# v1.net
KiCad netlist of a schematic drawn in EAGLE
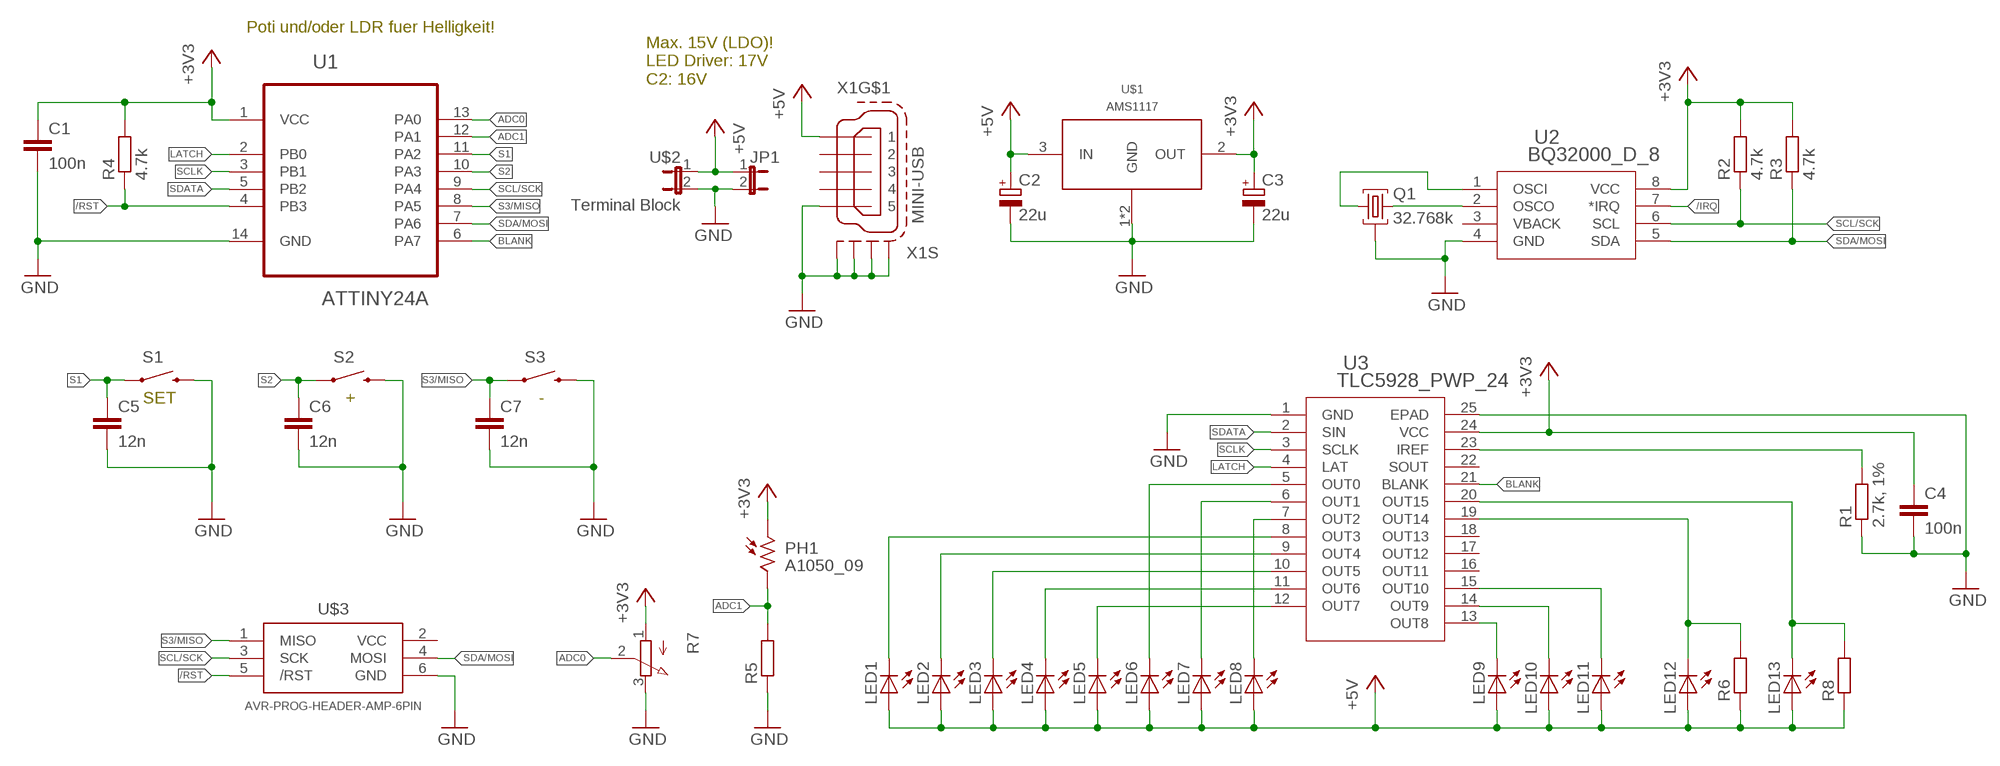
[diagram p0: schematic, sheet 1]
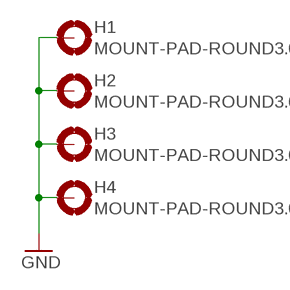
[diagram p1: schematic, sheet 2]

(export (version "E")
  (design (tool "Eeschema 10.0.6"))
  (components
    (comp (ref "C1")
      (value "100n")
      (footprint "eagle-import:C0603")
      (libsource (lib "eagle-import") (part "C-EUC0603"))
    )
    (comp (ref "C2")
      (value "22u")
      (footprint "eagle-import:153CLV-0505")
      (libsource (lib "eagle-import") (part "CPOL-EU153CLV-0505"))
    )
    (comp (ref "C3")
      (value "22u")
      (footprint "eagle-import:153CLV-0505")
      (libsource (lib "eagle-import") (part "CPOL-EU153CLV-0505"))
    )
    (comp (ref "C4")
      (value "100n")
      (footprint "eagle-import:C0603")
      (libsource (lib "eagle-import") (part "C-EUC0603"))
    )
    (comp (ref "C5")
      (value "12n")
      (footprint "eagle-import:C0603")
      (libsource (lib "eagle-import") (part "C-EUC0603"))
    )
    (comp (ref "C6")
      (value "12n")
      (footprint "eagle-import:C0603")
      (libsource (lib "eagle-import") (part "C-EUC0603"))
    )
    (comp (ref "C7")
      (value "12n")
      (footprint "eagle-import:C0603")
      (libsource (lib "eagle-import") (part "C-EUC0603"))
    )
    (comp (ref "JP1")
      (value "JP1E")
      (footprint "eagle-import:JP1")
      (libsource (lib "eagle-import") (part "JP1E"))
    )
    (comp (ref "LED1")
      (value "LEDCHIP-LED0603")
      (footprint "eagle-import:CHIP-LED0603")
      (libsource (lib "eagle-import") (part "LEDCHIP-LED0603"))
    )
    (comp (ref "LED2")
      (value "LEDCHIP-LED0603")
      (footprint "eagle-import:CHIP-LED0603")
      (libsource (lib "eagle-import") (part "LEDCHIP-LED0603"))
    )
    (comp (ref "LED3")
      (value "LEDCHIP-LED0603")
      (footprint "eagle-import:CHIP-LED0603")
      (libsource (lib "eagle-import") (part "LEDCHIP-LED0603"))
    )
    (comp (ref "LED4")
      (value "LEDCHIP-LED0603")
      (footprint "eagle-import:CHIP-LED0603")
      (libsource (lib "eagle-import") (part "LEDCHIP-LED0603"))
    )
    (comp (ref "LED5")
      (value "LEDCHIP-LED0603")
      (footprint "eagle-import:CHIP-LED0603")
      (libsource (lib "eagle-import") (part "LEDCHIP-LED0603"))
    )
    (comp (ref "LED6")
      (value "LEDCHIP-LED0603")
      (footprint "eagle-import:CHIP-LED0603")
      (libsource (lib "eagle-import") (part "LEDCHIP-LED0603"))
    )
    (comp (ref "LED7")
      (value "LEDCHIP-LED0603")
      (footprint "eagle-import:CHIP-LED0603")
      (libsource (lib "eagle-import") (part "LEDCHIP-LED0603"))
    )
    (comp (ref "LED8")
      (value "LEDCHIP-LED0603")
      (footprint "eagle-import:CHIP-LED0603")
      (libsource (lib "eagle-import") (part "LEDCHIP-LED0603"))
    )
    (comp (ref "LED9")
      (value "LEDCHIP-LED0603")
      (footprint "eagle-import:CHIP-LED0603")
      (libsource (lib "eagle-import") (part "LEDCHIP-LED0603"))
    )
    (comp (ref "LED10")
      (value "LEDCHIP-LED0603")
      (footprint "eagle-import:CHIP-LED0603")
      (libsource (lib "eagle-import") (part "LEDCHIP-LED0603"))
    )
    (comp (ref "LED11")
      (value "LEDCHIP-LED0603")
      (footprint "eagle-import:CHIP-LED0603")
      (libsource (lib "eagle-import") (part "LEDCHIP-LED0603"))
    )
    (comp (ref "LED12")
      (value "LEDCHIP-LED0603")
      (footprint "eagle-import:CHIP-LED0603")
      (libsource (lib "eagle-import") (part "LEDCHIP-LED0603"))
    )
    (comp (ref "LED13")
      (value "LEDCHIP-LED0603")
      (footprint "eagle-import:CHIP-LED0603")
      (libsource (lib "eagle-import") (part "LEDCHIP-LED0603"))
    )
    (comp (ref "PH1")
      (value "A1050_09")
      (footprint "eagle-import:T0-46-A10XX")
      (libsource (lib "eagle-import") (part "A1050_09"))
    )
    (comp (ref "Q1")
      (value "32.768k")
      (footprint "eagle-import:TC38")
      (libsource (lib "eagle-import") (part "CRYSTAL_TC38_SHIELD"))
    )
    (comp (ref "R1")
      (value "2.7k, 1%")
      (footprint "eagle-import:R1206")
      (libsource (lib "eagle-import") (part "R-EU_R1206"))
    )
    (comp (ref "R2")
      (value "4.7k")
      (footprint "eagle-import:R0603")
      (libsource (lib "eagle-import") (part "R-EU_R0603"))
    )
    (comp (ref "R3")
      (value "4.7k")
      (footprint "eagle-import:R0603")
      (libsource (lib "eagle-import") (part "R-EU_R0603"))
    )
    (comp (ref "R4")
      (value "4.7k")
      (footprint "eagle-import:R0603")
      (libsource (lib "eagle-import") (part "R-EU_R0603"))
    )
    (comp (ref "R5")
      (value "R-EU_R0603")
      (footprint "eagle-import:R0603")
      (libsource (lib "eagle-import") (part "R-EU_R0603"))
    )
    (comp (ref "R6")
      (value "R-EU_R0603")
      (footprint "eagle-import:R0603")
      (libsource (lib "eagle-import") (part "R-EU_R0603"))
    )
    (comp (ref "R7")
      (value "3RP/1610N")
      (footprint "eagle-import:3RP_1610N")
      (libsource (lib "eagle-import") (part "3RP/1610N"))
    )
    (comp (ref "R8")
      (value "R-EU_R0603")
      (footprint "eagle-import:R0603")
      (libsource (lib "eagle-import") (part "R-EU_R0603"))
    )
    (comp (ref "S1")
      (value "SWITCH-MOMENTARY-2PTH")
      (footprint "eagle-import:TACTILE-PTH")
      (libsource (lib "eagle-import") (part "SWITCH-MOMENTARY-2PTH"))
    )
    (comp (ref "S2")
      (value "SWITCH-MOMENTARY-2PTH")
      (footprint "eagle-import:TACTILE-PTH")
      (libsource (lib "eagle-import") (part "SWITCH-MOMENTARY-2PTH"))
    )
    (comp (ref "S3")
      (value "SWITCH-MOMENTARY-2PTH")
      (footprint "eagle-import:TACTILE-PTH")
      (libsource (lib "eagle-import") (part "SWITCH-MOMENTARY-2PTH"))
    )
    (comp (ref "U$1")
      (value "AMS1117")
      (footprint "eagle-import:DCY4")
      (libsource (lib "eagle-import") (part "AMS1117"))
    )
    (comp (ref "U$2")
      (value "Terminal Block")
      (footprint "eagle-import:BASTLI_SCREW_TERMINAL_SMALL")
      (libsource (lib "eagle-import") (part "BASTLI_SCREW_TERMINAL_SMALL"))
    )
    (comp (ref "U$3")
      (value "AVR-PROG-HEADER-AMP-6PIN")
      (footprint "eagle-import:AMP-TMM-1-0-06")
      (libsource (lib "eagle-import") (part "AVR-PROG-HEADER-AMP-6PIN"))
    )
    (comp (ref "U1")
      (value "ATTINY24A")
      (footprint "eagle-import:SOIC127P600X175-14N")
      (fields (field (name "MPN") "ATTINY24A-SSU"))
      (libsource (lib "eagle-import") (part "ATTINY24A-SSU"))
    )
    (comp (ref "U2")
      (value "BQ32000_D_8")
      (footprint "eagle-import:D8")
      (fields
        (field (name "GENERIC_PART_NUMBER") "BQ32000")
        (field (name "MANUFACTURER") "Texas Instruments")
      )
      (libsource (lib "eagle-import") (part "BQ32000_D_8"))
    )
    (comp (ref "U3")
      (value "TLC5928_PWP_24")
      (footprint "eagle-import:PWP24_4P87X2P4")
      (fields
        (field (name "GENERIC_PART_NUMBER") "TLC5928")
        (field (name "MANUFACTURER") "Texas Instruments")
        (field (name "MANUFACTURER_PART_NUMBER") "tlc5928_pwp_24")
      )
      (libsource (lib "eagle-import") (part "TLC5928_PWP_24"))
    )
    (comp (ref "X1")
      (value "MINI-USB")
      (footprint "eagle-import:32005-201")
      (libsource (lib "eagle-import") (part "MINI-USB-SCHIELD-32005-201"))
    )
    (comp (ref "H1")
      (value "MOUNT-PAD-ROUND3.0")
      (footprint "eagle-import:3,0-PAD")
      (libsource (lib "eagle-import") (part "MOUNT-PAD-ROUND3.0"))
    )
    (comp (ref "H2")
      (value "MOUNT-PAD-ROUND3.0")
      (footprint "eagle-import:3,0-PAD")
      (libsource (lib "eagle-import") (part "MOUNT-PAD-ROUND3.0"))
    )
    (comp (ref "H3")
      (value "MOUNT-PAD-ROUND3.0")
      (footprint "eagle-import:3,0-PAD")
      (libsource (lib "eagle-import") (part "MOUNT-PAD-ROUND3.0"))
    )
    (comp (ref "H4")
      (value "MOUNT-PAD-ROUND3.0")
      (footprint "eagle-import:3,0-PAD")
      (libsource (lib "eagle-import") (part "MOUNT-PAD-ROUND3.0"))
    )
  )
  (nets
    (net (code "1") (name "+3V3") (class "Default")
      (node (ref "C1") (pin "1") (pinfunction "1_1") (pintype "passive"))
      (node (ref "C3") (pin "+") (pinfunction "+_+") (pintype "passive"))
      (node (ref "C4") (pin "1") (pinfunction "1_1") (pintype "passive"))
      (node (ref "PH1") (pin "1") (pinfunction "1_1") (pintype "passive"))
      (node (ref "R2") (pin "2") (pinfunction "2_2") (pintype "passive"))
      (node (ref "R3") (pin "2") (pinfunction "2_2") (pintype "passive"))
      (node (ref "R4") (pin "2") (pinfunction "2_2") (pintype "passive"))
      (node (ref "R7") (pin "1") (pinfunction "A_1") (pintype "passive"))
      (node (ref "U$1") (pin "2") (pinfunction "OUT_2") (pintype "power_in"))
      (node (ref "U1") (pin "1") (pinfunction "VCC_1") (pintype "power_in"))
      (node (ref "U2") (pin "8") (pinfunction "VCC_8") (pintype "power_in"))
      (node (ref "U3") (pin "24") (pinfunction "VCC_24") (pintype "power_in"))
    )
    (net (code "2") (name "+5V") (class "Default")
      (node (ref "C2") (pin "+") (pinfunction "+_+") (pintype "passive"))
      (node (ref "JP1") (pin "1") (pinfunction "1_1") (pintype "passive"))
      (node (ref "LED1") (pin "A") (pinfunction "A_A") (pintype "passive"))
      (node (ref "LED10") (pin "A") (pinfunction "A_A") (pintype "passive"))
      (node (ref "LED11") (pin "A") (pinfunction "A_A") (pintype "passive"))
      (node (ref "LED12") (pin "A") (pinfunction "A_A") (pintype "passive"))
      (node (ref "LED13") (pin "A") (pinfunction "A_A") (pintype "passive"))
      (node (ref "LED2") (pin "A") (pinfunction "A_A") (pintype "passive"))
      (node (ref "LED3") (pin "A") (pinfunction "A_A") (pintype "passive"))
      (node (ref "LED4") (pin "A") (pinfunction "A_A") (pintype "passive"))
      (node (ref "LED5") (pin "A") (pinfunction "A_A") (pintype "passive"))
      (node (ref "LED6") (pin "A") (pinfunction "A_A") (pintype "passive"))
      (node (ref "LED7") (pin "A") (pinfunction "A_A") (pintype "passive"))
      (node (ref "LED8") (pin "A") (pinfunction "A_A") (pintype "passive"))
      (node (ref "LED9") (pin "A") (pinfunction "A_A") (pintype "passive"))
      (node (ref "R6") (pin "1") (pinfunction "1_1") (pintype "passive"))
      (node (ref "R8") (pin "1") (pinfunction "1_1") (pintype "passive"))
      (node (ref "U$1") (pin "3") (pinfunction "IN_3") (pintype "power_in"))
      (node (ref "U$2") (pin "1") (pinfunction "1_1") (pintype "passive"))
      (node (ref "X1") (pin "1") (pinfunction "1_1") (pintype "passive"))
    )
    (net (code "3") (name "ADC0") (class "Default")
      (node (ref "R7") (pin "2") (pinfunction "S_2") (pintype "passive"))
      (node (ref "U1") (pin "13") (pinfunction "PA0_13") (pintype "bidirectional"))
    )
    (net (code "4") (name "ADC1") (class "Default")
      (node (ref "PH1") (pin "2") (pinfunction "2_2") (pintype "passive"))
      (node (ref "R5") (pin "2") (pinfunction "2_2") (pintype "passive"))
      (node (ref "U1") (pin "12") (pinfunction "PA1_12") (pintype "bidirectional"))
    )
    (net (code "5") (name "BLANK") (class "Default")
      (node (ref "U1") (pin "6") (pinfunction "PA7_6") (pintype "bidirectional"))
      (node (ref "U3") (pin "21") (pinfunction "BLANK_21") (pintype "input"))
    )
    (net (code "6") (name "GND") (class "Default")
      (node (ref "C1") (pin "2") (pinfunction "2_2") (pintype "passive"))
      (node (ref "C2") (pin "-") (pinfunction "-_-") (pintype "passive"))
      (node (ref "C3") (pin "-") (pinfunction "-_-") (pintype "passive"))
      (node (ref "C4") (pin "2") (pinfunction "2_2") (pintype "passive"))
      (node (ref "C5") (pin "2") (pinfunction "2_2") (pintype "passive"))
      (node (ref "C6") (pin "2") (pinfunction "2_2") (pintype "passive"))
      (node (ref "C7") (pin "2") (pinfunction "2_2") (pintype "passive"))
      (node (ref "H1") (pin "B3,0") (pinfunction "MOUNT_B3,0") (pintype "passive"))
      (node (ref "H2") (pin "B3,0") (pinfunction "MOUNT_B3,0") (pintype "passive"))
      (node (ref "H3") (pin "B3,0") (pinfunction "MOUNT_B3,0") (pintype "passive"))
      (node (ref "H4") (pin "B3,0") (pinfunction "MOUNT_B3,0") (pintype "passive"))
      (node (ref "JP1") (pin "2") (pinfunction "2_2") (pintype "passive"))
      (node (ref "Q1") (pin "1") (pinfunction "2_1") (pintype "passive"))
      (node (ref "R1") (pin "1") (pinfunction "1_1") (pintype "passive"))
      (node (ref "R5") (pin "1") (pinfunction "1_1") (pintype "passive"))
      (node (ref "R7") (pin "3") (pinfunction "E_3") (pintype "passive"))
      (node (ref "S1") (pin "3") (pinfunction "2_3") (pintype "passive"))
      (node (ref "S2") (pin "3") (pinfunction "2_3") (pintype "passive"))
      (node (ref "S3") (pin "3") (pinfunction "2_3") (pintype "passive"))
      (node (ref "U$1") (pin "1") (pinfunction "GND_1") (pintype "input"))
      (node (ref "U$1") (pin "4") (pinfunction "GND_4") (pintype "input"))
      (node (ref "U$2") (pin "2") (pinfunction "2_2") (pintype "passive"))
      (node (ref "U$3") (pin "6") (pinfunction "GND_6") (pintype "bidirectional"))
      (node (ref "U1") (pin "14") (pinfunction "GND_14") (pintype "power_in"))
      (node (ref "U2") (pin "4") (pinfunction "GND_4") (pintype "power_in"))
      (node (ref "U3") (pin "1") (pinfunction "GND_1") (pintype "power_in"))
      (node (ref "U3") (pin "25") (pinfunction "EPAD_25") (pintype "passive"))
      (node (ref "X1") (pin "5") (pinfunction "5_5") (pintype "passive"))
      (node (ref "X1") (pin "M1") (pinfunction "S1_M1") (pintype "passive"))
      (node (ref "X1") (pin "M2") (pinfunction "S2_M2") (pintype "passive"))
      (node (ref "X1") (pin "M3") (pinfunction "S3_M3") (pintype "passive"))
      (node (ref "X1") (pin "M4") (pinfunction "S4_M4") (pintype "passive"))
    )
    (net (code "7") (name "LATCH") (class "Default")
      (node (ref "U1") (pin "2") (pinfunction "PB0_2") (pintype "bidirectional"))
      (node (ref "U3") (pin "4") (pinfunction "LAT_4") (pintype "input"))
    )
    (net (code "8") (name "Net-(Q1-1)") (class "Default")
      (node (ref "Q1") (pin "2") (pinfunction "1_2") (pintype "passive"))
      (node (ref "U2") (pin "1") (pinfunction "OSCI_1") (pintype "input"))
    )
    (net (code "9") (name "Net-(U2-OSCO)") (class "Default")
      (node (ref "Q1") (pin "3") (pinfunction "3_3") (pintype "passive"))
      (node (ref "U2") (pin "2") (pinfunction "OSCO_2") (pintype "passive"))
    )
    (net (code "10") (name "Net-(U3-IREF)") (class "Default")
      (node (ref "R1") (pin "2") (pinfunction "2_2") (pintype "passive"))
      (node (ref "U3") (pin "23") (pinfunction "IREF_23") (pintype "bidirectional"))
    )
    (net (code "11") (name "Net-(U3-OUT0)") (class "Default")
      (node (ref "LED6") (pin "C") (pinfunction "C_C") (pintype "passive"))
      (node (ref "U3") (pin "5") (pinfunction "OUT0_5") (pintype "output"))
    )
    (net (code "12") (name "Net-(U3-OUT1)") (class "Default")
      (node (ref "LED7") (pin "C") (pinfunction "C_C") (pintype "passive"))
      (node (ref "U3") (pin "6") (pinfunction "OUT1_6") (pintype "output"))
    )
    (net (code "13") (name "Net-(U3-OUT2)") (class "Default")
      (node (ref "LED8") (pin "C") (pinfunction "C_C") (pintype "passive"))
      (node (ref "U3") (pin "7") (pinfunction "OUT2_7") (pintype "output"))
    )
    (net (code "14") (name "Net-(U3-OUT3)") (class "Default")
      (node (ref "LED1") (pin "C") (pinfunction "C_C") (pintype "passive"))
      (node (ref "U3") (pin "8") (pinfunction "OUT3_8") (pintype "output"))
    )
    (net (code "15") (name "Net-(U3-OUT4)") (class "Default")
      (node (ref "LED2") (pin "C") (pinfunction "C_C") (pintype "passive"))
      (node (ref "U3") (pin "9") (pinfunction "OUT4_9") (pintype "output"))
    )
    (net (code "16") (name "Net-(U3-OUT5)") (class "Default")
      (node (ref "LED3") (pin "C") (pinfunction "C_C") (pintype "passive"))
      (node (ref "U3") (pin "10") (pinfunction "OUT5_10") (pintype "output"))
    )
    (net (code "17") (name "Net-(U3-OUT6)") (class "Default")
      (node (ref "LED4") (pin "C") (pinfunction "C_C") (pintype "passive"))
      (node (ref "U3") (pin "11") (pinfunction "OUT6_11") (pintype "output"))
    )
    (net (code "18") (name "Net-(U3-OUT7)") (class "Default")
      (node (ref "LED5") (pin "C") (pinfunction "C_C") (pintype "passive"))
      (node (ref "U3") (pin "12") (pinfunction "OUT7_12") (pintype "output"))
    )
    (net (code "19") (name "Net-(U3-OUT8)") (class "Default")
      (node (ref "LED9") (pin "C") (pinfunction "C_C") (pintype "passive"))
      (node (ref "U3") (pin "13") (pinfunction "OUT8_13") (pintype "output"))
    )
    (net (code "20") (name "Net-(U3-OUT9)") (class "Default")
      (node (ref "LED10") (pin "C") (pinfunction "C_C") (pintype "passive"))
      (node (ref "U3") (pin "14") (pinfunction "OUT9_14") (pintype "output"))
    )
    (net (code "21") (name "Net-(U3-OUT10)") (class "Default")
      (node (ref "LED11") (pin "C") (pinfunction "C_C") (pintype "passive"))
      (node (ref "U3") (pin "15") (pinfunction "OUT10_15") (pintype "output"))
    )
    (net (code "22") (name "Net-(U3-OUT14)") (class "Default")
      (node (ref "LED12") (pin "C") (pinfunction "C_C") (pintype "passive"))
      (node (ref "R6") (pin "2") (pinfunction "2_2") (pintype "passive"))
      (node (ref "U3") (pin "19") (pinfunction "OUT14_19") (pintype "output"))
    )
    (net (code "23") (name "Net-(U3-OUT15)") (class "Default")
      (node (ref "LED13") (pin "C") (pinfunction "C_C") (pintype "passive"))
      (node (ref "R8") (pin "2") (pinfunction "2_2") (pintype "passive"))
      (node (ref "U3") (pin "20") (pinfunction "OUT15_20") (pintype "output"))
    )
    (net (code "24") (name "S1") (class "Default")
      (node (ref "C5") (pin "1") (pinfunction "1_1") (pintype "passive"))
      (node (ref "S1") (pin "1") (pinfunction "1_1") (pintype "passive"))
      (node (ref "U1") (pin "11") (pinfunction "PA2_11") (pintype "bidirectional"))
    )
    (net (code "25") (name "S2") (class "Default")
      (node (ref "C6") (pin "1") (pinfunction "1_1") (pintype "passive"))
      (node (ref "S2") (pin "1") (pinfunction "1_1") (pintype "passive"))
      (node (ref "U1") (pin "10") (pinfunction "PA3_10") (pintype "bidirectional"))
    )
    (net (code "26") (name "S3{slash}MISO") (class "Default")
      (node (ref "C7") (pin "1") (pinfunction "1_1") (pintype "passive"))
      (node (ref "S3") (pin "1") (pinfunction "1_1") (pintype "passive"))
      (node (ref "U$3") (pin "1") (pinfunction "MISO_1") (pintype "bidirectional"))
      (node (ref "U1") (pin "8") (pinfunction "PA5_8") (pintype "bidirectional"))
    )
    (net (code "27") (name "SCLK") (class "Default")
      (node (ref "U1") (pin "3") (pinfunction "PB1_3") (pintype "bidirectional"))
      (node (ref "U3") (pin "3") (pinfunction "SCLK_3") (pintype "input"))
    )
    (net (code "28") (name "SCL{slash}SCK") (class "Default")
      (node (ref "R2") (pin "1") (pinfunction "1_1") (pintype "passive"))
      (node (ref "U$3") (pin "3") (pinfunction "SCK_3") (pintype "bidirectional"))
      (node (ref "U1") (pin "9") (pinfunction "PA4_9") (pintype "bidirectional"))
      (node (ref "U2") (pin "6") (pinfunction "SCL_6") (pintype "input"))
    )
    (net (code "29") (name "SDATA") (class "Default")
      (node (ref "U1") (pin "5") (pinfunction "PB2_5") (pintype "bidirectional"))
      (node (ref "U3") (pin "2") (pinfunction "SIN_2") (pintype "input"))
    )
    (net (code "30") (name "SDA{slash}MOSI") (class "Default")
      (node (ref "R3") (pin "1") (pinfunction "1_1") (pintype "passive"))
      (node (ref "U$3") (pin "4") (pinfunction "MOSI_4") (pintype "bidirectional"))
      (node (ref "U1") (pin "7") (pinfunction "PA6_7") (pintype "bidirectional"))
      (node (ref "U2") (pin "5") (pinfunction "SDA_5") (pintype "bidirectional"))
    )
    (net (code "31") (name "VBACK") (class "Default")
      (node (ref "U2") (pin "3") (pinfunction "VBACK_3") (pintype "power_in"))
    )
    (net (code "32") (name "unconnected-(U$3-VCC-Pad2)") (class "Default")
      (node (ref "U$3") (pin "2") (pinfunction "VCC_2") (pintype "bidirectional"))
    )
    (net (code "33") (name "unconnected-(U3-OUT11-Pad16)") (class "Default")
      (node (ref "U3") (pin "16") (pinfunction "OUT11_16") (pintype "output"))
    )
    (net (code "34") (name "unconnected-(U3-OUT12-Pad17)") (class "Default")
      (node (ref "U3") (pin "17") (pinfunction "OUT12_17") (pintype "output"))
    )
    (net (code "35") (name "unconnected-(U3-OUT13-Pad18)") (class "Default")
      (node (ref "U3") (pin "18") (pinfunction "OUT13_18") (pintype "output"))
    )
    (net (code "36") (name "unconnected-(U3-SOUT-Pad22)") (class "Default")
      (node (ref "U3") (pin "22") (pinfunction "SOUT_22") (pintype "output"))
    )
    (net (code "37") (name "unconnected-(X1-Pad2)") (class "Default")
      (node (ref "X1") (pin "2") (pinfunction "2_2") (pintype "passive"))
    )
    (net (code "38") (name "unconnected-(X1-Pad3)") (class "Default")
      (node (ref "X1") (pin "3") (pinfunction "3_3") (pintype "passive"))
    )
    (net (code "39") (name "unconnected-(X1-Pad4)") (class "Default")
      (node (ref "X1") (pin "4") (pinfunction "4_4") (pintype "passive"))
    )
    (net (code "40") (name "{slash}IRQ") (class "Default")
      (node (ref "U2") (pin "7") (pinfunction "*IRQ_7") (pintype "passive"))
    )
    (net (code "41") (name "{slash}RST") (class "Default")
      (node (ref "R4") (pin "1") (pinfunction "1_1") (pintype "passive"))
      (node (ref "U$3") (pin "5") (pinfunction "/RST_5") (pintype "bidirectional"))
      (node (ref "U1") (pin "4") (pinfunction "PB3_4") (pintype "bidirectional"))
    )
  )
)
